# TopLevel.net
KiCad netlist of a schematic drawn in Altium Designer
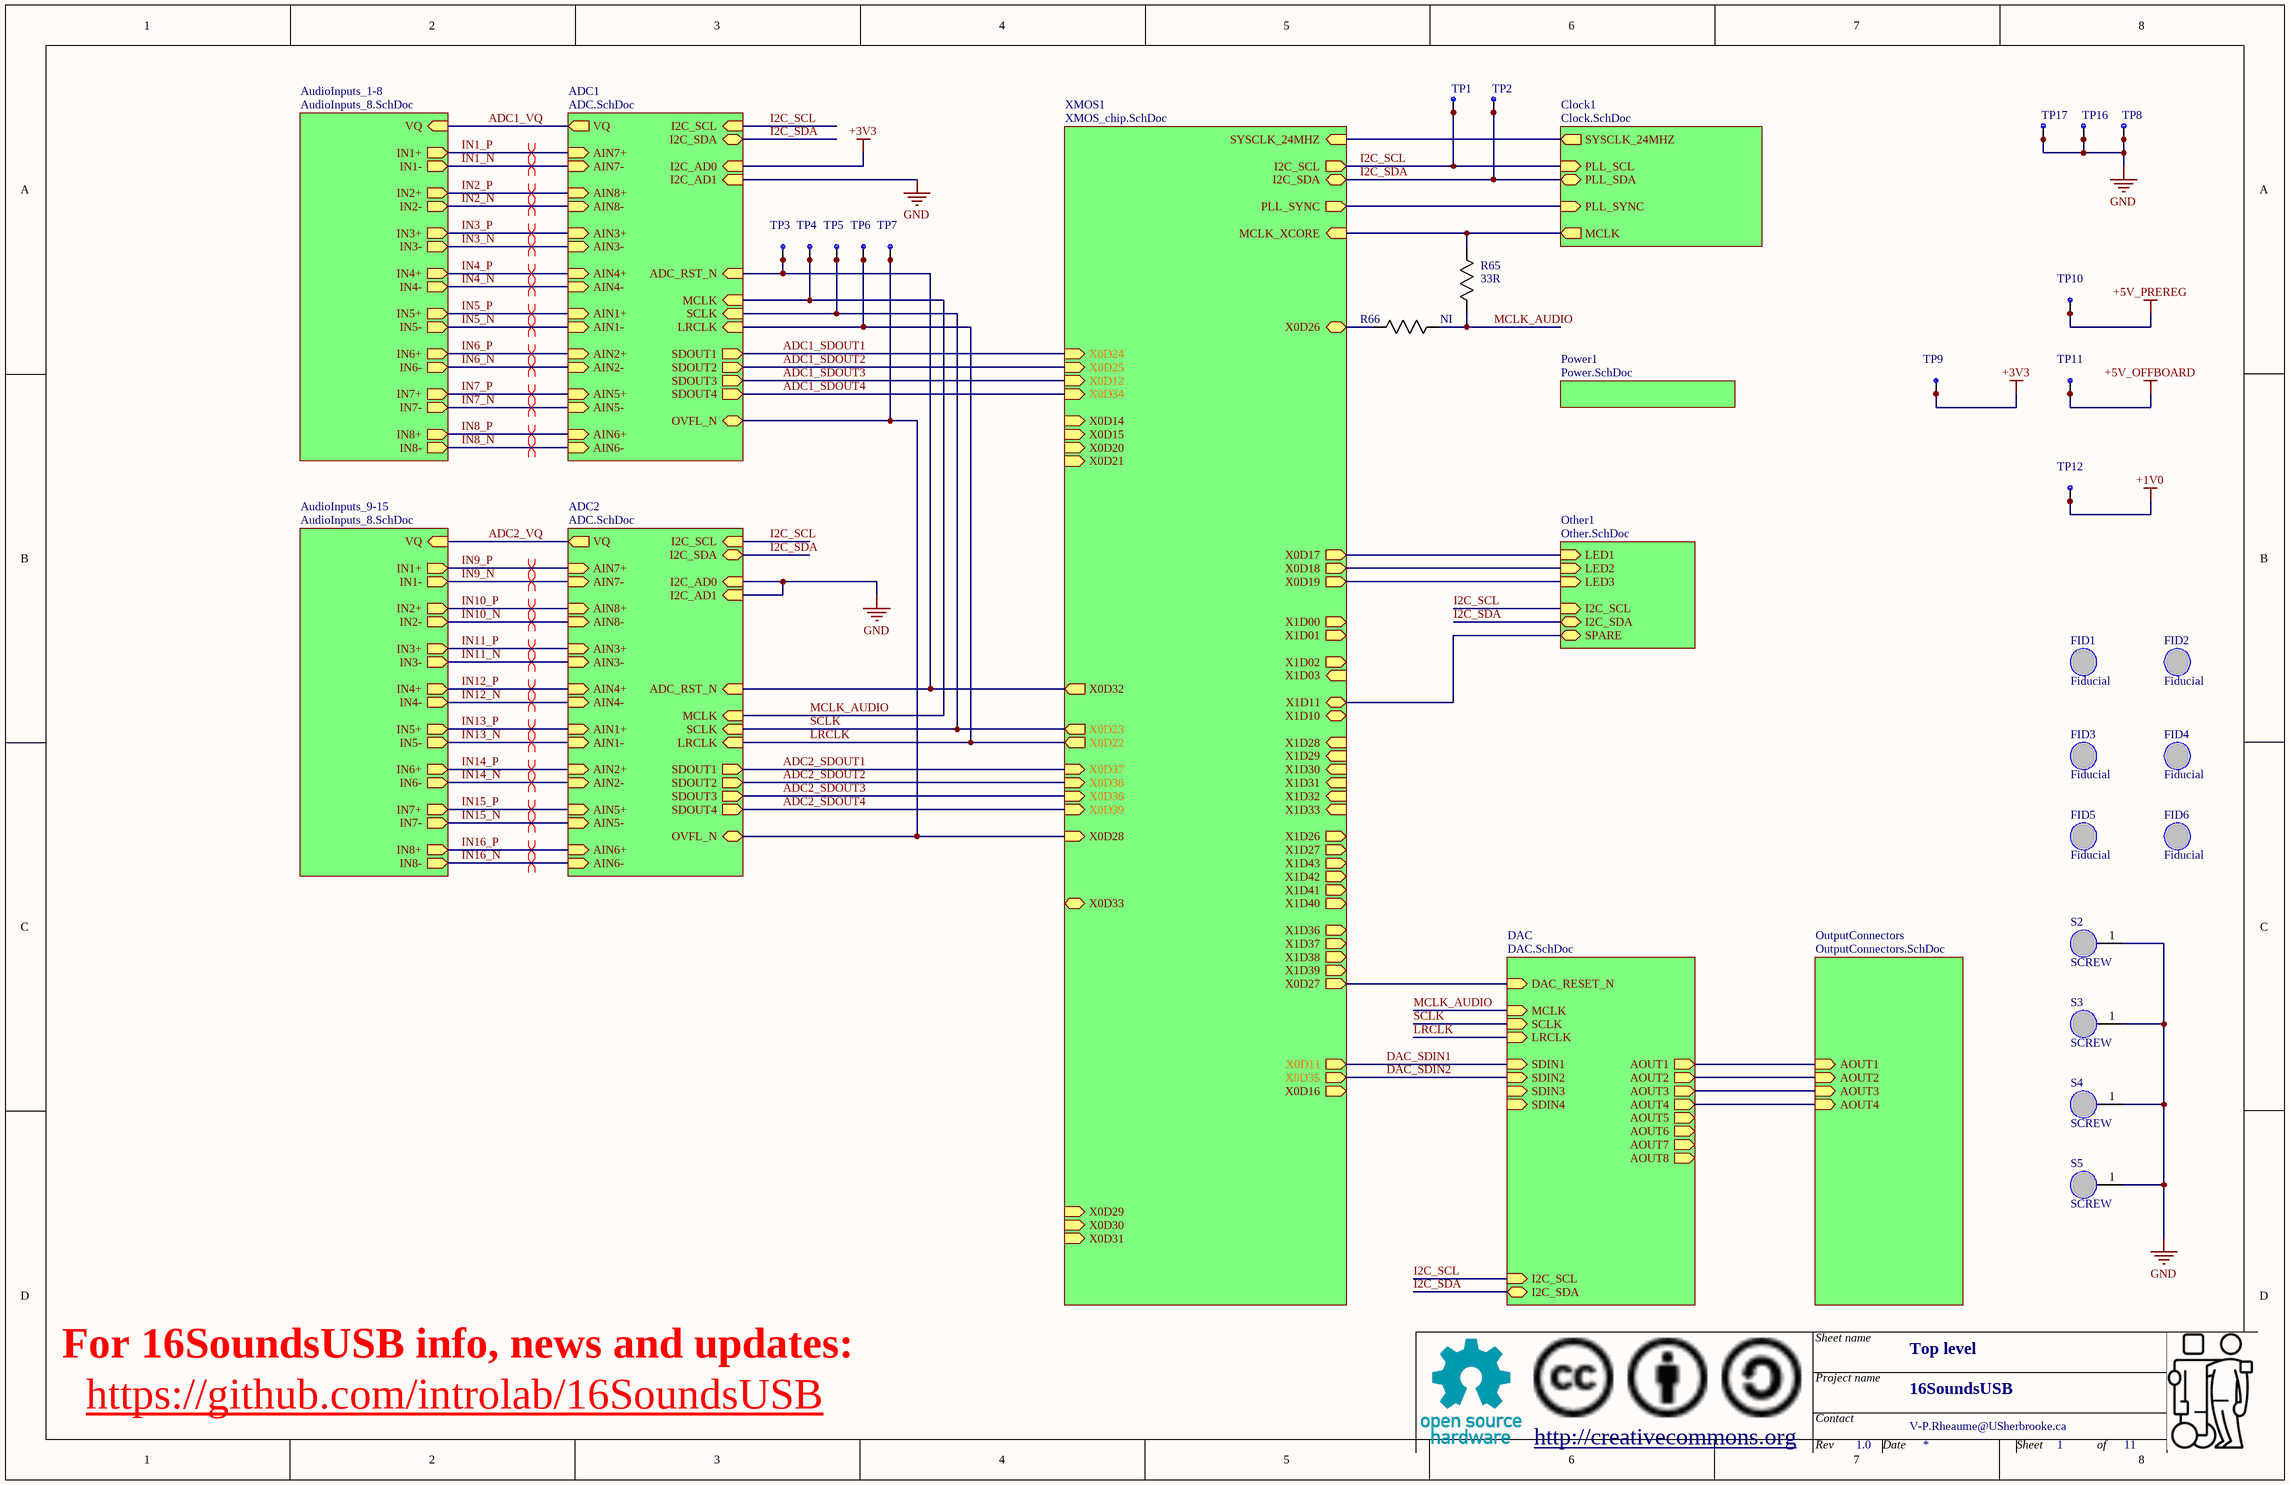
[diagram p0: TopLevel.SchDoc]

(export (version "E")
  (design (tool "Eeschema 10.0.6"))
  (components
    (comp (ref "FID1")
      (value "Fiducial")
      (footprint "FIDUCIAL")
      (libsource (lib "INTER_2014") (part "Fiducial"))
    )
    (comp (ref "FID2")
      (value "Fiducial")
      (footprint "FIDUCIAL")
      (libsource (lib "INTER_2014") (part "Fiducial"))
    )
    (comp (ref "FID3")
      (value "Fiducial")
      (footprint "FIDUCIAL")
      (libsource (lib "INTER_2014") (part "Fiducial"))
    )
    (comp (ref "FID4")
      (value "Fiducial")
      (footprint "FIDUCIAL")
      (libsource (lib "INTER_2014") (part "Fiducial"))
    )
    (comp (ref "FID5")
      (value "Fiducial")
      (footprint "FIDUCIAL")
      (libsource (lib "INTER_2014") (part "Fiducial"))
    )
    (comp (ref "FID6")
      (value "Fiducial")
      (footprint "FIDUCIAL")
      (libsource (lib "INTER_2014") (part "Fiducial"))
    )
    (comp (ref "R65")
      (value "33R")
      (footprint "0603")
      (description "Resistor")
      (libsource (lib "INTER_2014") (part "Resistor"))
    )
    (comp (ref "R66")
      (value "Resistor")
      (footprint "0603")
      (fields (field (name "NI") "NI"))
      (libsource (lib "INTER_2014") (part "Resistor"))
    )
    (comp (ref "S2")
      (value "SCREW")
      (footprint "SCREW_4_40")
      (description "Screw hole")
      (libsource (lib "INTER_2014") (part "SCREW"))
    )
    (comp (ref "S3")
      (value "SCREW")
      (footprint "SCREW_4_40")
      (description "Screw hole")
      (libsource (lib "INTER_2014") (part "SCREW"))
    )
    (comp (ref "S4")
      (value "SCREW")
      (footprint "SCREW_4_40")
      (description "Screw hole")
      (libsource (lib "INTER_2014") (part "SCREW"))
    )
    (comp (ref "S5")
      (value "SCREW")
      (footprint "SCREW_4_40")
      (description "Screw hole")
      (libsource (lib "INTER_2014") (part "SCREW"))
    )
    (comp (ref "TP1")
      (value "TESTPOINT")
      (footprint "0603")
      (description "Test point")
      (fields (field (name "MFG") "TE"))
      (libsource (lib "INTER_2014") (part "TESTPOINT"))
    )
    (comp (ref "TP2")
      (value "TESTPOINT")
      (footprint "0603")
      (description "Test point")
      (fields (field (name "MFG") "TE"))
      (libsource (lib "INTER_2014") (part "TESTPOINT"))
    )
    (comp (ref "TP3")
      (value "TESTPOINT")
      (footprint "0603")
      (description "Test point")
      (fields (field (name "MFG") "TE"))
      (libsource (lib "INTER_2014") (part "TESTPOINT"))
    )
    (comp (ref "TP4")
      (value "TESTPOINT")
      (footprint "0603")
      (description "Test point")
      (fields (field (name "MFG") "TE"))
      (libsource (lib "INTER_2014") (part "TESTPOINT"))
    )
    (comp (ref "TP5")
      (value "TESTPOINT")
      (footprint "0603")
      (description "Test point")
      (fields (field (name "MFG") "TE"))
      (libsource (lib "INTER_2014") (part "TESTPOINT"))
    )
    (comp (ref "TP6")
      (value "TESTPOINT")
      (footprint "0603")
      (description "Test point")
      (fields (field (name "MFG") "TE"))
      (libsource (lib "INTER_2014") (part "TESTPOINT"))
    )
    (comp (ref "TP7")
      (value "TESTPOINT")
      (footprint "0603")
      (description "Test point")
      (fields (field (name "MFG") "TE"))
      (libsource (lib "INTER_2014") (part "TESTPOINT"))
    )
    (comp (ref "TP8")
      (value "TESTPOINT")
      (footprint "1206")
      (description "Test point")
      (fields (field (name "MFG") "Harwin"))
      (libsource (lib "INTER_2014") (part "TESTPOINT"))
    )
    (comp (ref "TP9")
      (value "TESTPOINT")
      (footprint "0603")
      (description "Test point")
      (fields (field (name "MFG") "TE"))
      (libsource (lib "INTER_2014") (part "TESTPOINT"))
    )
    (comp (ref "TP10")
      (value "TESTPOINT")
      (footprint "0603")
      (description "Test point")
      (fields (field (name "MFG") "TE"))
      (libsource (lib "INTER_2014") (part "TESTPOINT"))
    )
    (comp (ref "TP11")
      (value "TESTPOINT")
      (footprint "0603")
      (description "Test point")
      (fields (field (name "MFG") "TE"))
      (libsource (lib "INTER_2014") (part "TESTPOINT"))
    )
    (comp (ref "TP12")
      (value "TESTPOINT")
      (footprint "0603")
      (description "Test point")
      (fields (field (name "MFG") "TE"))
      (libsource (lib "INTER_2014") (part "TESTPOINT"))
    )
    (comp (ref "TP16")
      (value "TESTPOINT")
      (footprint "1206")
      (description "Test point")
      (fields (field (name "MFG") "Harwin"))
      (libsource (lib "INTER_2014") (part "TESTPOINT"))
    )
    (comp (ref "TP17")
      (value "TESTPOINT")
      (footprint "1206")
      (description "Test point")
      (fields (field (name "MFG") "Harwin"))
      (libsource (lib "INTER_2014") (part "TESTPOINT"))
    )
  )
  (nets
    (net (code "1") (name "+1V0") (class "Default")
      (node (ref "TP12") (pin "1") (pintype "passive"))
      (node (ref "TP12") (pin "2") (pintype "passive"))
    )
    (net (code "2") (name "+3V3") (class "Default")
      (node (ref "TP9") (pin "1") (pintype "passive"))
      (node (ref "TP9") (pin "2") (pintype "passive"))
    )
    (net (code "3") (name "+5V_OFFBOARD") (class "Default")
      (node (ref "TP11") (pin "1") (pintype "passive"))
      (node (ref "TP11") (pin "2") (pintype "passive"))
    )
    (net (code "4") (name "+5V_PREREG") (class "Default")
      (node (ref "TP10") (pin "1") (pintype "passive"))
      (node (ref "TP10") (pin "2") (pintype "passive"))
    )
    (net (code "25") (name "/I2C_SCL") (class "Default")
      (node (ref "TP1") (pin "1") (pintype "passive"))
      (node (ref "TP1") (pin "2") (pintype "passive"))
    )
    (net (code "26") (name "/I2C_SDA") (class "Default")
      (node (ref "TP2") (pin "1") (pintype "passive"))
      (node (ref "TP2") (pin "2") (pintype "passive"))
    )
    (net (code "59") (name "/LRCLK") (class "Default")
      (node (ref "TP6") (pin "1") (pintype "passive"))
      (node (ref "TP6") (pin "2") (pintype "passive"))
    )
    (net (code "60") (name "/MCLK") (class "Default") (node (ref "R65") (pin "2") (pintype "passive")))
    (net (code "61") (name "/MCLK_AUDIO") (class "Default")
      (node (ref "R65") (pin "1") (pintype "passive"))
      (node (ref "R66") (pin "2") (pintype "passive"))
      (node (ref "TP4") (pin "1") (pintype "passive"))
      (node (ref "TP4") (pin "2") (pintype "passive"))
    )
    (net (code "62") (name "/OVFL_N") (class "Default")
      (node (ref "TP7") (pin "1") (pintype "passive"))
      (node (ref "TP7") (pin "2") (pintype "passive"))
    )
    (net (code "64") (name "/SCLK") (class "Default")
      (node (ref "TP5") (pin "1") (pintype "passive"))
      (node (ref "TP5") (pin "2") (pintype "passive"))
    )
    (net (code "77") (name "/X0D26") (class "Default") (node (ref "R66") (pin "1") (pintype "passive")))
    (net (code "82") (name "/X0D32") (class "Default")
      (node (ref "TP3") (pin "1") (pintype "passive"))
      (node (ref "TP3") (pin "2") (pintype "passive"))
    )
    (net (code "105") (name "GND") (class "Default")
      (node (ref "S2") (pin "1") (pintype "passive"))
      (node (ref "S3") (pin "1") (pintype "passive"))
      (node (ref "S4") (pin "1") (pintype "passive"))
      (node (ref "S5") (pin "1") (pintype "passive"))
      (node (ref "TP16") (pin "1") (pintype "passive"))
      (node (ref "TP16") (pin "2") (pintype "passive"))
      (node (ref "TP17") (pin "1") (pintype "passive"))
      (node (ref "TP17") (pin "2") (pintype "passive"))
      (node (ref "TP8") (pin "1") (pintype "passive"))
      (node (ref "TP8") (pin "2") (pintype "passive"))
    )
    (net (code "106") (name "unconnected-(FID1-Pad0)") (class "Default")
      (node (ref "FID1") (pin "0") (pintype "passive"))
    )
    (net (code "107") (name "unconnected-(FID2-Pad0)") (class "Default")
      (node (ref "FID2") (pin "0") (pintype "passive"))
    )
    (net (code "108") (name "unconnected-(FID3-Pad0)") (class "Default")
      (node (ref "FID3") (pin "0") (pintype "passive"))
    )
    (net (code "109") (name "unconnected-(FID4-Pad0)") (class "Default")
      (node (ref "FID4") (pin "0") (pintype "passive"))
    )
    (net (code "110") (name "unconnected-(FID5-Pad0)") (class "Default")
      (node (ref "FID5") (pin "0") (pintype "passive"))
    )
    (net (code "111") (name "unconnected-(FID6-Pad0)") (class "Default")
      (node (ref "FID6") (pin "0") (pintype "passive"))
    )
  )
)
